# foe-scale.net
KiCad netlist of a schematic drawn in EAGLE
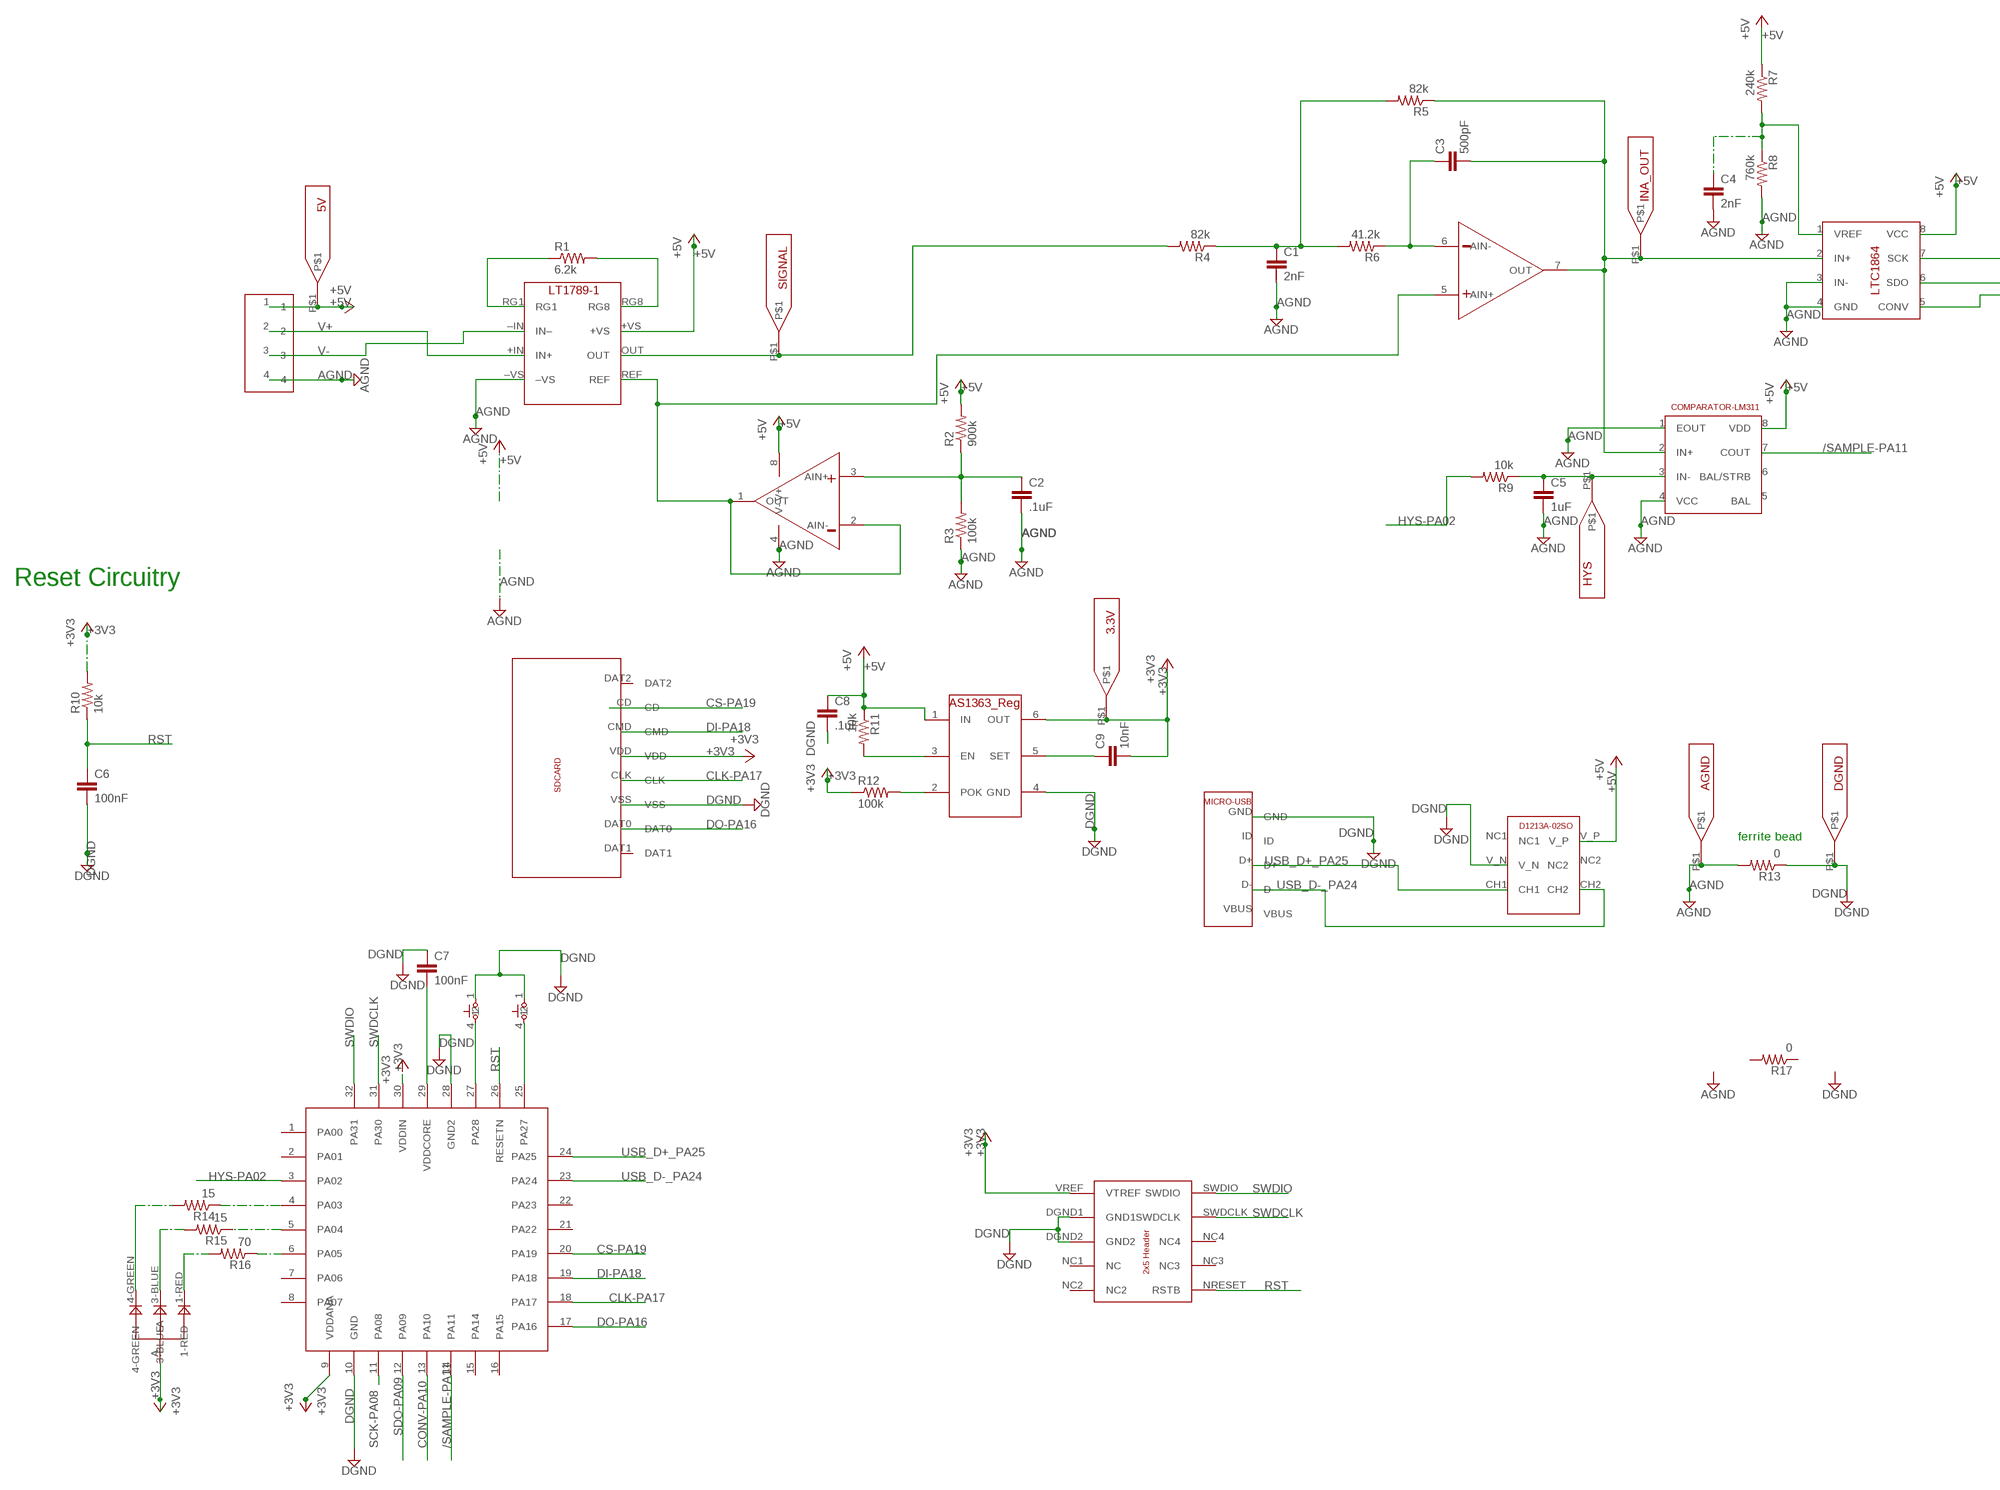
[diagram p0: schematic, sheet 1, part 1 of 2]
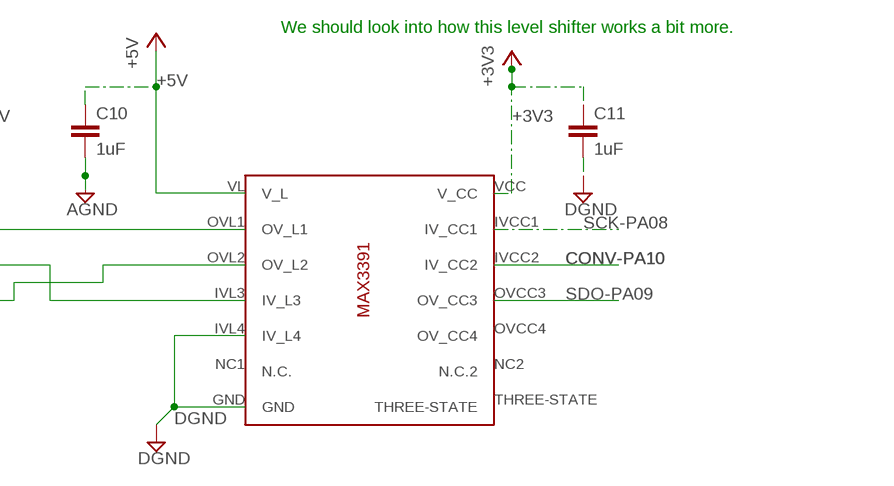
[diagram p1: schematic, sheet 1, part 2 of 2]

(export (version "E")
  (design (tool "Eeschema 10.0.6"))
  (components
    (comp (ref "3.3V")
      (value "TEST_POINT")
      (footprint "eagle-import:TEST_POINT")
      (libsource (lib "eagle-import") (part "TEST_POINT"))
    )
    (comp (ref "5V")
      (value "TEST_POINT")
      (footprint "eagle-import:TEST_POINT")
      (libsource (lib "eagle-import") (part "TEST_POINT"))
    )
    (comp (ref "AGND")
      (value "TEST_POINT")
      (footprint "eagle-import:TEST_POINT")
      (libsource (lib "eagle-import") (part "TEST_POINT"))
    )
    (comp (ref "AS1363")
      (value "3.3V_AS1363")
      (footprint "eagle-import:SOT23-6")
      (libsource (lib "eagle-import") (part "3.3V_AS1363"))
    )
    (comp (ref "C1")
      (value "2nF")
      (footprint "eagle-import:C0805K")
      (libsource (lib "eagle-import") (part "C-EUC0805K"))
    )
    (comp (ref "C2")
      (value ".1uF")
      (footprint "eagle-import:C0805K")
      (libsource (lib "eagle-import") (part "C-EUC0805K"))
    )
    (comp (ref "C3")
      (value "500pF")
      (footprint "eagle-import:C0805K")
      (libsource (lib "eagle-import") (part "C-EUC0805K"))
    )
    (comp (ref "C4")
      (value "2nF")
      (footprint "eagle-import:C0805K")
      (libsource (lib "eagle-import") (part "C-EUC0805K"))
    )
    (comp (ref "C5")
      (value "1uF")
      (footprint "eagle-import:C0805K")
      (libsource (lib "eagle-import") (part "C-EUC0805K"))
    )
    (comp (ref "C6")
      (value "100nF")
      (footprint "eagle-import:C0805K")
      (libsource (lib "eagle-import") (part "C-EUC0805K"))
    )
    (comp (ref "C7")
      (value "100nF")
      (footprint "eagle-import:C0805K")
      (libsource (lib "eagle-import") (part "C-EUC0805K"))
    )
    (comp (ref "C8")
      (value ".1uF")
      (footprint "eagle-import:C0805K")
      (libsource (lib "eagle-import") (part "C-EUC0805K"))
    )
    (comp (ref "C9")
      (value "10nF")
      (footprint "eagle-import:C0805K")
      (libsource (lib "eagle-import") (part "C-EUC0805K"))
    )
    (comp (ref "C10")
      (value "1uF")
      (footprint "eagle-import:C0805K")
      (libsource (lib "eagle-import") (part "C-EUC0805K"))
    )
    (comp (ref "C11")
      (value "1uF")
      (footprint "eagle-import:C0805K")
      (libsource (lib "eagle-import") (part "C-EUC0805K"))
    )
    (comp (ref "D1")
      (value "D1213A-DIODE-ARRAY")
      (footprint "eagle-import:SOT26-DIODE-ARRAY")
      (libsource (lib "eagle-import") (part "D1213A-DIODE-ARRAY"))
    )
    (comp (ref "DBG1")
      (value "DEBUGHEAD")
      (footprint "eagle-import:DEBUGHEAD")
      (libsource (lib "eagle-import") (part "DEBUGHEAD"))
    )
    (comp (ref "DGND")
      (value "TEST_POINT")
      (footprint "eagle-import:TEST_POINT")
      (libsource (lib "eagle-import") (part "TEST_POINT"))
    )
    (comp (ref "HYS")
      (value "TEST_POINT")
      (footprint "eagle-import:TEST_POINT")
      (libsource (lib "eagle-import") (part "TEST_POINT"))
    )
    (comp (ref "INA_OUT")
      (value "TEST_POINT")
      (footprint "eagle-import:TEST_POINT")
      (libsource (lib "eagle-import") (part "TEST_POINT"))
    )
    (comp (ref "R1")
      (value "6.2k")
      (footprint "eagle-import:R0805")
      (libsource (lib "eagle-import") (part "R-US_R0805"))
    )
    (comp (ref "R2")
      (value "900k")
      (footprint "eagle-import:R0805")
      (libsource (lib "eagle-import") (part "R-US_R0805"))
    )
    (comp (ref "R3")
      (value "100k")
      (footprint "eagle-import:R0805")
      (libsource (lib "eagle-import") (part "R-US_R0805"))
    )
    (comp (ref "R4")
      (value "82k")
      (footprint "eagle-import:R0805")
      (libsource (lib "eagle-import") (part "R-US_R0805"))
    )
    (comp (ref "R5")
      (value "82k")
      (footprint "eagle-import:R0805")
      (libsource (lib "eagle-import") (part "R-US_R0805"))
    )
    (comp (ref "R6")
      (value "41.2k")
      (footprint "eagle-import:R0805")
      (libsource (lib "eagle-import") (part "R-US_R0805"))
    )
    (comp (ref "R7")
      (value "240k")
      (footprint "eagle-import:R0805")
      (libsource (lib "eagle-import") (part "R-US_R0805"))
    )
    (comp (ref "R8")
      (value "760k")
      (footprint "eagle-import:R0805")
      (libsource (lib "eagle-import") (part "R-US_R0805"))
    )
    (comp (ref "R9")
      (value "10k")
      (footprint "eagle-import:R0805")
      (libsource (lib "eagle-import") (part "R-US_R0805"))
    )
    (comp (ref "R10")
      (value "10k")
      (footprint "eagle-import:R0805")
      (libsource (lib "eagle-import") (part "R-US_R0805"))
    )
    (comp (ref "R11")
      (value "10k")
      (footprint "eagle-import:R0805")
      (libsource (lib "eagle-import") (part "R-US_R0805"))
    )
    (comp (ref "R12")
      (value "100k")
      (footprint "eagle-import:R0805")
      (libsource (lib "eagle-import") (part "R-US_R0805"))
    )
    (comp (ref "R13")
      (value "0")
      (footprint "eagle-import:R0805")
      (libsource (lib "eagle-import") (part "R-US_R0805"))
    )
    (comp (ref "R14")
      (value "15")
      (footprint "eagle-import:R0805")
      (libsource (lib "eagle-import") (part "R-US_R0805"))
    )
    (comp (ref "R15")
      (value "15")
      (footprint "eagle-import:R0805")
      (libsource (lib "eagle-import") (part "R-US_R0805"))
    )
    (comp (ref "R16")
      (value "70")
      (footprint "eagle-import:R0805")
      (libsource (lib "eagle-import") (part "R-US_R0805"))
    )
    (comp (ref "R17")
      (value "0")
      (footprint "eagle-import:R0805")
      (libsource (lib "eagle-import") (part "R-US_R0805"))
    )
    (comp (ref "SIGNAL")
      (value "TEST_POINT")
      (footprint "eagle-import:TEST_POINT")
      (libsource (lib "eagle-import") (part "TEST_POINT"))
    )
    (comp (ref "U$1")
      (value "1X04")
      (footprint "eagle-import:1X04")
      (libsource (lib "eagle-import") (part "1X04"))
    )
    (comp (ref "U$2")
      (value "LT1789-1-INSTR-AMP")
      (footprint "eagle-import:S8-LT1789-1")
      (libsource (lib "eagle-import") (part "LT1789-1-INSTR-AMP"))
    )
    (comp (ref "U$3")
      (value "LMC6482")
      (footprint "eagle-import:SOIC8")
      (libsource (lib "eagle-import") (part "LMC6482"))
    )
    (comp (ref "U$6")
      (value "ADC-LTC1864")
      (footprint "eagle-import:SOIC8")
      (libsource (lib "eagle-import") (part "ADC-LTC1864"))
    )
    (comp (ref "U$7")
      (value "LEVEL-SHIFTER")
      (footprint "eagle-import:TSSOP-14")
      (libsource (lib "eagle-import") (part "LEVEL-SHIFTER"))
    )
    (comp (ref "U$8")
      (value "SDCARD_JACK")
      (footprint "eagle-import:MICRO_SDCARD")
      (libsource (lib "eagle-import") (part "SDCARD_JACK"))
    )
    (comp (ref "U$10")
      (value "RGBLED")
      (footprint "eagle-import:RGBLED")
      (libsource (lib "eagle-import") (part "RGBLED"))
    )
    (comp (ref "U$11")
      (value "BUTTON_THRU")
      (footprint "eagle-import:PUSHBTN")
      (libsource (lib "eagle-import") (part "BUTTON_THRU"))
    )
    (comp (ref "U$12")
      (value "BUTTON_THRU")
      (footprint "eagle-import:PUSHBTN")
      (libsource (lib "eagle-import") (part "BUTTON_THRU"))
    )
    (comp (ref "U$13")
      (value "MICRO-USB-CONNECTOR")
      (footprint "eagle-import:MICRO-USB-CONNECTOR")
      (libsource (lib "eagle-import") (part "MICRO-USB-CONNECTOR"))
    )
    (comp (ref "U1")
      (value "LM311")
      (footprint "eagle-import:SOIC8")
      (libsource (lib "eagle-import") (part "LM311"))
    )
    (comp (ref "U2")
      (value "SAMD21E")
      (footprint "eagle-import:TQFP32-08")
      (libsource (lib "eagle-import") (part "SAMD21E"))
    )
  )
  (nets
    (net (code "1") (name "+3V3") (class "Default")
      (node (ref "3.3V") (pin "P$1") (pinfunction "P$1_P$1") (pintype "bidirectional"))
      (node (ref "AS1363") (pin "6") (pinfunction "OUT_6") (pintype "bidirectional"))
      (node (ref "C11") (pin "1") (pinfunction "1_1") (pintype "passive"))
      (node (ref "C9") (pin "2") (pinfunction "2_2") (pintype "passive"))
      (node (ref "DBG1") (pin "VREF") (pinfunction "VTREF_VREF") (pintype "bidirectional"))
      (node (ref "R10") (pin "2") (pinfunction "2_2") (pintype "passive"))
      (node (ref "R12") (pin "1") (pinfunction "1_1") (pintype "passive"))
      (node (ref "U$10") (pin "A") (pinfunction "A_A") (pintype "bidirectional"))
      (node (ref "U$7") (pin "VCC") (pinfunction "V_CC_VCC") (pintype "bidirectional"))
      (node (ref "U$8") (pin "VDD") (pinfunction "VDD_VDD") (pintype "bidirectional"))
      (node (ref "U2") (pin "30") (pinfunction "VDDIN_30") (pintype "bidirectional"))
      (node (ref "U2") (pin "9") (pinfunction "VDDANA_9") (pintype "bidirectional"))
    )
    (net (code "2") (name "+5V") (class "Default")
      (node (ref "5V") (pin "P$1") (pinfunction "P$1_P$1") (pintype "bidirectional"))
      (node (ref "AS1363") (pin "1") (pinfunction "IN_1") (pintype "bidirectional"))
      (node (ref "C10") (pin "1") (pinfunction "1_1") (pintype "passive"))
      (node (ref "C8") (pin "1") (pinfunction "1_1") (pintype "passive"))
      (node (ref "D1") (pin "V_P") (pinfunction "V_P_V_P") (pintype "bidirectional"))
      (node (ref "R11") (pin "1") (pinfunction "1_1") (pintype "passive"))
      (node (ref "R2") (pin "2") (pinfunction "2_2") (pintype "passive"))
      (node (ref "R7") (pin "1") (pinfunction "1_1") (pintype "passive"))
      (node (ref "U$1") (pin "1") (pinfunction "1_1") (pintype "bidirectional"))
      (node (ref "U$2") (pin "+VS") (pinfunction "+VS_+VS") (pintype "bidirectional"))
      (node (ref "U$3") (pin "8") (pinfunction "V+_8") (pintype "bidirectional"))
      (node (ref "U$6") (pin "8") (pinfunction "VCC_8") (pintype "bidirectional"))
      (node (ref "U$7") (pin "VL") (pinfunction "V_L_VL") (pintype "bidirectional"))
      (node (ref "U1") (pin "8") (pinfunction "VDD_8") (pintype "bidirectional"))
    )
    (net (code "3") (name "/CLK-PA17") (class "Default")
      (node (ref "U$8") (pin "CLK") (pinfunction "CLK_CLK") (pintype "bidirectional"))
      (node (ref "U2") (pin "18") (pinfunction "PA17_18") (pintype "bidirectional"))
    )
    (net (code "4") (name "/CONV-PA10") (class "Default")
      (node (ref "U$7") (pin "IVCC2") (pinfunction "IV_CC2_IVCC2") (pintype "bidirectional"))
      (node (ref "U2") (pin "13") (pinfunction "PA10_13") (pintype "bidirectional"))
    )
    (net (code "5") (name "/CS-PA19") (class "Default")
      (node (ref "U$8") (pin "CD") (pinfunction "CD_CD") (pintype "bidirectional"))
      (node (ref "U2") (pin "20") (pinfunction "PA19_20") (pintype "bidirectional"))
    )
    (net (code "6") (name "/DI-PA18") (class "Default")
      (node (ref "U$8") (pin "CMD") (pinfunction "CMD_CMD") (pintype "bidirectional"))
      (node (ref "U2") (pin "19") (pinfunction "PA18_19") (pintype "bidirectional"))
    )
    (net (code "7") (name "/DO-PA16") (class "Default")
      (node (ref "U$8") (pin "DAT0") (pinfunction "DAT0_DAT0") (pintype "bidirectional"))
      (node (ref "U2") (pin "17") (pinfunction "PA16_17") (pintype "bidirectional"))
    )
    (net (code "8") (name "/HYS-PA02") (class "Default")
      (node (ref "R9") (pin "2") (pinfunction "2_2") (pintype "passive"))
      (node (ref "U2") (pin "3") (pinfunction "PA02_3") (pintype "bidirectional"))
    )
    (net (code "9") (name "/RST") (class "Default")
      (node (ref "C6") (pin "1") (pinfunction "1_1") (pintype "passive"))
      (node (ref "DBG1") (pin "NRESET") (pinfunction "RSTB_NRESET") (pintype "bidirectional"))
      (node (ref "R10") (pin "1") (pinfunction "1_1") (pintype "passive"))
      (node (ref "U2") (pin "26") (pinfunction "RESETN_26") (pintype "bidirectional"))
    )
    (net (code "10") (name "/SCK-PA08") (class "Default")
      (node (ref "U$7") (pin "IVCC1") (pinfunction "IV_CC1_IVCC1") (pintype "bidirectional"))
      (node (ref "U2") (pin "11") (pinfunction "PA08_11") (pintype "bidirectional"))
    )
    (net (code "11") (name "/SDO-PA09") (class "Default")
      (node (ref "U$7") (pin "OVCC3") (pinfunction "OV_CC3_OVCC3") (pintype "bidirectional"))
      (node (ref "U2") (pin "12") (pinfunction "PA09_12") (pintype "bidirectional"))
    )
    (net (code "12") (name "/SWDCLK") (class "Default")
      (node (ref "DBG1") (pin "SWDCLK") (pinfunction "SWDCLK_SWDCLK") (pintype "bidirectional"))
      (node (ref "U2") (pin "31") (pinfunction "PA30_31") (pintype "bidirectional"))
    )
    (net (code "13") (name "/SWDIO") (class "Default")
      (node (ref "DBG1") (pin "SWDIO") (pinfunction "SWDIO_SWDIO") (pintype "bidirectional"))
      (node (ref "U2") (pin "32") (pinfunction "PA31_32") (pintype "bidirectional"))
    )
    (net (code "14") (name "/USB_D+_PA25") (class "Default")
      (node (ref "D1") (pin "CH1") (pinfunction "CH1_CH1") (pintype "bidirectional"))
      (node (ref "U$13") (pin "D+") (pinfunction "D+_D+") (pintype "bidirectional"))
      (node (ref "U2") (pin "24") (pinfunction "PA25_24") (pintype "bidirectional"))
    )
    (net (code "15") (name "/USB_D-_PA24") (class "Default")
      (node (ref "D1") (pin "CH2") (pinfunction "CH2_CH2") (pintype "bidirectional"))
      (node (ref "U$13") (pin "D-") (pinfunction "D-_D-") (pintype "bidirectional"))
      (node (ref "U2") (pin "23") (pinfunction "PA24_23") (pintype "bidirectional"))
    )
    (net (code "16") (name "/V+") (class "Default")
      (node (ref "U$1") (pin "2") (pinfunction "2_2") (pintype "bidirectional"))
      (node (ref "U$2") (pin "+IN") (pinfunction "IN+_+IN") (pintype "bidirectional"))
    )
    (net (code "17") (name "/V-") (class "Default")
      (node (ref "U$1") (pin "3") (pinfunction "3_3") (pintype "bidirectional"))
      (node (ref "U$2") (pin "–IN") (pinfunction "IN–_–IN") (pintype "bidirectional"))
    )
    (net (code "18") (name "/{slash}SAMPLE-PA11") (class "Default")
      (node (ref "U1") (pin "7") (pinfunction "COUT_7") (pintype "bidirectional"))
      (node (ref "U2") (pin "14") (pinfunction "PA11_14") (pintype "bidirectional"))
    )
    (net (code "19") (name "AGND") (class "Default")
      (node (ref "AGND") (pin "P$1") (pinfunction "P$1_P$1") (pintype "bidirectional"))
      (node (ref "C1") (pin "2") (pinfunction "2_2") (pintype "passive"))
      (node (ref "C10") (pin "2") (pinfunction "2_2") (pintype "passive"))
      (node (ref "C2") (pin "2") (pinfunction "2_2") (pintype "passive"))
      (node (ref "C4") (pin "2") (pinfunction "2_2") (pintype "passive"))
      (node (ref "C5") (pin "2") (pinfunction "2_2") (pintype "passive"))
      (node (ref "R13") (pin "2") (pinfunction "2_2") (pintype "passive"))
      (node (ref "R3") (pin "1") (pinfunction "1_1") (pintype "passive"))
      (node (ref "R8") (pin "2") (pinfunction "2_2") (pintype "passive"))
      (node (ref "U$1") (pin "4") (pinfunction "4_4") (pintype "bidirectional"))
      (node (ref "U$2") (pin "–VS") (pinfunction "–VS_–VS") (pintype "bidirectional"))
      (node (ref "U$3") (pin "4") (pinfunction "V-_4") (pintype "bidirectional"))
      (node (ref "U$6") (pin "3") (pinfunction "IN-_3") (pintype "bidirectional"))
      (node (ref "U$6") (pin "4") (pinfunction "GND_4") (pintype "bidirectional"))
      (node (ref "U1") (pin "1") (pinfunction "EOUT_1") (pintype "bidirectional"))
      (node (ref "U1") (pin "4") (pinfunction "VCC_4") (pintype "bidirectional"))
    )
    (net (code "20") (name "DGND") (class "Default")
      (node (ref "AS1363") (pin "4") (pinfunction "GND_4") (pintype "bidirectional"))
      (node (ref "C11") (pin "2") (pinfunction "2_2") (pintype "passive"))
      (node (ref "C6") (pin "2") (pinfunction "2_2") (pintype "passive"))
      (node (ref "C7") (pin "1") (pinfunction "1_1") (pintype "passive"))
      (node (ref "C8") (pin "2") (pinfunction "2_2") (pintype "passive"))
      (node (ref "D1") (pin "V_N") (pinfunction "V_N_V_N") (pintype "bidirectional"))
      (node (ref "DBG1") (pin "DGND1") (pinfunction "GND1_DGND1") (pintype "bidirectional"))
      (node (ref "DBG1") (pin "DGND2") (pinfunction "GND2_DGND2") (pintype "bidirectional"))
      (node (ref "DGND") (pin "P$1") (pinfunction "P$1_P$1") (pintype "bidirectional"))
      (node (ref "R13") (pin "1") (pinfunction "1_1") (pintype "passive"))
      (node (ref "U$11") (pin "1") (pinfunction "1_1") (pintype "bidirectional"))
      (node (ref "U$12") (pin "1") (pinfunction "1_1") (pintype "bidirectional"))
      (node (ref "U$13") (pin "GND") (pinfunction "GND_GND") (pintype "bidirectional"))
      (node (ref "U$7") (pin "GND") (pinfunction "GND_GND") (pintype "bidirectional"))
      (node (ref "U$7") (pin "IVL4") (pinfunction "IV_L4_IVL4") (pintype "bidirectional"))
      (node (ref "U$8") (pin "VSS") (pinfunction "VSS_VSS") (pintype "bidirectional"))
      (node (ref "U2") (pin "10") (pinfunction "GND_10") (pintype "bidirectional"))
      (node (ref "U2") (pin "28") (pinfunction "GND2_28") (pintype "bidirectional"))
    )
    (net (code "21") (name "Net-(AS1363-EN)") (class "Default")
      (node (ref "AS1363") (pin "3") (pinfunction "EN_3") (pintype "bidirectional"))
      (node (ref "R11") (pin "2") (pinfunction "2_2") (pintype "passive"))
    )
    (net (code "22") (name "Net-(AS1363-POK)") (class "Default")
      (node (ref "AS1363") (pin "2") (pinfunction "POK_2") (pintype "bidirectional"))
      (node (ref "R12") (pin "2") (pinfunction "2_2") (pintype "passive"))
    )
    (net (code "23") (name "Net-(AS1363-SET)") (class "Default")
      (node (ref "AS1363") (pin "5") (pinfunction "SET_5") (pintype "bidirectional"))
      (node (ref "C9") (pin "1") (pinfunction "1_1") (pintype "passive"))
    )
    (net (code "24") (name "Net-(C1-Pad1)") (class "Default")
      (node (ref "C1") (pin "1") (pinfunction "1_1") (pintype "passive"))
      (node (ref "R4") (pin "1") (pinfunction "1_1") (pintype "passive"))
      (node (ref "R5") (pin "2") (pinfunction "2_2") (pintype "passive"))
      (node (ref "R6") (pin "2") (pinfunction "2_2") (pintype "passive"))
    )
    (net (code "25") (name "Net-(R1-Pad1)") (class "Default")
      (node (ref "R1") (pin "1") (pinfunction "1_1") (pintype "passive"))
      (node (ref "U$2") (pin "RG1") (pinfunction "RG1_RG1") (pintype "bidirectional"))
    )
    (net (code "26") (name "Net-(R1-Pad2)") (class "Default")
      (node (ref "R1") (pin "2") (pinfunction "2_2") (pintype "passive"))
      (node (ref "U$2") (pin "RG8") (pinfunction "RG8_RG8") (pintype "bidirectional"))
    )
    (net (code "27") (name "Net-(R4-Pad2)") (class "Default")
      (node (ref "R4") (pin "2") (pinfunction "2_2") (pintype "passive"))
      (node (ref "SIGNAL") (pin "P$1") (pinfunction "P$1_P$1") (pintype "bidirectional"))
      (node (ref "U$2") (pin "OUT") (pinfunction "OUT_OUT") (pintype "bidirectional"))
    )
    (net (code "28") (name "Net-(R14-Pad2)") (class "Default")
      (node (ref "R14") (pin "2") (pinfunction "2_2") (pintype "passive"))
      (node (ref "U$10") (pin "4-GREEN") (pinfunction "4-GREEN_4-GREEN") (pintype "bidirectional"))
    )
    (net (code "29") (name "Net-(R15-Pad2)") (class "Default")
      (node (ref "R15") (pin "2") (pinfunction "2_2") (pintype "passive"))
      (node (ref "U$10") (pin "3-BLUE") (pinfunction "3-BLUE_3-BLUE") (pintype "bidirectional"))
    )
    (net (code "30") (name "Net-(R16-Pad2)") (class "Default")
      (node (ref "R16") (pin "2") (pinfunction "2_2") (pintype "passive"))
      (node (ref "U$10") (pin "1-RED") (pinfunction "1-RED_1-RED") (pintype "bidirectional"))
    )
    (net (code "31") (name "Net-(U$3A-AIN+)") (class "Default")
      (node (ref "C2") (pin "1") (pinfunction "1_1") (pintype "passive"))
      (node (ref "R2") (pin "1") (pinfunction "1_1") (pintype "passive"))
      (node (ref "R3") (pin "2") (pinfunction "2_2") (pintype "passive"))
      (node (ref "U$3") (pin "3") (pinfunction "AIN+_3") (pintype "bidirectional"))
    )
    (net (code "32") (name "Net-(U$3A-AIN-)") (class "Default")
      (node (ref "U$2") (pin "REF") (pinfunction "REF_REF") (pintype "bidirectional"))
      (node (ref "U$3") (pin "1") (pinfunction "OUT_1") (pintype "bidirectional"))
      (node (ref "U$3") (pin "2") (pinfunction "AIN-_2") (pintype "bidirectional"))
      (node (ref "U$3") (pin "5") (pinfunction "AIN+_5") (pintype "bidirectional"))
    )
    (net (code "33") (name "Net-(U$3B-AIN-)") (class "Default")
      (node (ref "C3") (pin "1") (pinfunction "1_1") (pintype "passive"))
      (node (ref "R6") (pin "1") (pinfunction "1_1") (pintype "passive"))
      (node (ref "U$3") (pin "6") (pinfunction "AIN-_6") (pintype "bidirectional"))
    )
    (net (code "34") (name "Net-(U$3B-OUT)") (class "Default")
      (node (ref "C3") (pin "2") (pinfunction "2_2") (pintype "passive"))
      (node (ref "INA_OUT") (pin "P$1") (pinfunction "P$1_P$1") (pintype "bidirectional"))
      (node (ref "R5") (pin "1") (pinfunction "1_1") (pintype "passive"))
      (node (ref "U$3") (pin "7") (pinfunction "OUT_7") (pintype "bidirectional"))
      (node (ref "U$6") (pin "2") (pinfunction "IN+_2") (pintype "bidirectional"))
      (node (ref "U1") (pin "2") (pinfunction "IN+_2") (pintype "bidirectional"))
    )
    (net (code "35") (name "Net-(U$6-CONV)") (class "Default")
      (node (ref "U$6") (pin "5") (pinfunction "CONV_5") (pintype "bidirectional"))
      (node (ref "U$7") (pin "OVL2") (pinfunction "OV_L2_OVL2") (pintype "bidirectional"))
    )
    (net (code "36") (name "Net-(U$6-SCK)") (class "Default")
      (node (ref "U$6") (pin "7") (pinfunction "SCK_7") (pintype "bidirectional"))
      (node (ref "U$7") (pin "OVL1") (pinfunction "OV_L1_OVL1") (pintype "bidirectional"))
    )
    (net (code "37") (name "Net-(U$6-SDO)") (class "Default")
      (node (ref "U$6") (pin "6") (pinfunction "SDO_6") (pintype "bidirectional"))
      (node (ref "U$7") (pin "IVL3") (pinfunction "IV_L3_IVL3") (pintype "bidirectional"))
    )
    (net (code "38") (name "Net-(U$6-VREF)") (class "Default")
      (node (ref "C4") (pin "1") (pinfunction "1_1") (pintype "passive"))
      (node (ref "R7") (pin "2") (pinfunction "2_2") (pintype "passive"))
      (node (ref "R8") (pin "1") (pinfunction "1_1") (pintype "passive"))
      (node (ref "U$6") (pin "1") (pinfunction "VREF_1") (pintype "bidirectional"))
    )
    (net (code "39") (name "Net-(U$11-2)") (class "Default")
      (node (ref "U$11") (pin "4") (pinfunction "2_4") (pintype "bidirectional"))
      (node (ref "U2") (pin "25") (pinfunction "PA27_25") (pintype "bidirectional"))
    )
    (net (code "40") (name "Net-(U$12-2)") (class "Default")
      (node (ref "U$12") (pin "4") (pinfunction "2_4") (pintype "bidirectional"))
      (node (ref "U2") (pin "27") (pinfunction "PA28_27") (pintype "bidirectional"))
    )
    (net (code "41") (name "Net-(U1-IN-)") (class "Default")
      (node (ref "C5") (pin "1") (pinfunction "1_1") (pintype "passive"))
      (node (ref "HYS") (pin "P$1") (pinfunction "P$1_P$1") (pintype "bidirectional"))
      (node (ref "R9") (pin "1") (pinfunction "1_1") (pintype "passive"))
      (node (ref "U1") (pin "3") (pinfunction "IN-_3") (pintype "bidirectional"))
    )
    (net (code "42") (name "Net-(U2-PA03)") (class "Default")
      (node (ref "R14") (pin "1") (pinfunction "1_1") (pintype "passive"))
      (node (ref "U2") (pin "4") (pinfunction "PA03_4") (pintype "bidirectional"))
    )
    (net (code "43") (name "Net-(U2-PA04)") (class "Default")
      (node (ref "R15") (pin "1") (pinfunction "1_1") (pintype "passive"))
      (node (ref "U2") (pin "5") (pinfunction "PA04_5") (pintype "bidirectional"))
    )
    (net (code "44") (name "Net-(U2-PA05)") (class "Default")
      (node (ref "R16") (pin "1") (pinfunction "1_1") (pintype "passive"))
      (node (ref "U2") (pin "6") (pinfunction "PA05_6") (pintype "bidirectional"))
    )
    (net (code "45") (name "Net-(U2-VDDCORE)") (class "Default")
      (node (ref "C7") (pin "2") (pinfunction "2_2") (pintype "passive"))
      (node (ref "U2") (pin "29") (pinfunction "VDDCORE_29") (pintype "bidirectional"))
    )
    (net (code "46") (name "unconnected-(D1-PadNC1)") (class "Default")
      (node (ref "D1") (pin "NC1") (pinfunction "NC1_NC1") (pintype "bidirectional"))
    )
    (net (code "47") (name "unconnected-(D1-PadNC2)") (class "Default")
      (node (ref "D1") (pin "NC2") (pinfunction "NC2_NC2") (pintype "bidirectional"))
    )
    (net (code "48") (name "unconnected-(DBG1-NC-PadNC1)") (class "Default")
      (node (ref "DBG1") (pin "NC1") (pinfunction "NC_NC1") (pintype "bidirectional"))
    )
    (net (code "49") (name "unconnected-(DBG1-PadNC2)") (class "Default")
      (node (ref "DBG1") (pin "NC2") (pinfunction "NC2_NC2") (pintype "bidirectional"))
    )
    (net (code "50") (name "unconnected-(DBG1-PadNC3)") (class "Default")
      (node (ref "DBG1") (pin "NC3") (pinfunction "NC3_NC3") (pintype "bidirectional"))
    )
    (net (code "51") (name "unconnected-(DBG1-PadNC4)") (class "Default")
      (node (ref "DBG1") (pin "NC4") (pinfunction "NC4_NC4") (pintype "bidirectional"))
    )
    (net (code "52") (name "unconnected-(R17-Pad1)") (class "Default")
      (node (ref "R17") (pin "1") (pinfunction "1_1") (pintype "passive"))
    )
    (net (code "53") (name "unconnected-(R17-Pad2)") (class "Default")
      (node (ref "R17") (pin "2") (pinfunction "2_2") (pintype "passive"))
    )
    (net (code "54") (name "unconnected-(U$7-N.C.-PadNC1)") (class "Default")
      (node (ref "U$7") (pin "NC1") (pinfunction "N.C._NC1") (pintype "bidirectional"))
    )
    (net (code "55") (name "unconnected-(U$7-N.C.2-PadNC2)") (class "Default")
      (node (ref "U$7") (pin "NC2") (pinfunction "N.C.2_NC2") (pintype "bidirectional"))
    )
    (net (code "56") (name "unconnected-(U$7-OV_CC4-PadOVCC4)") (class "Default")
      (node (ref "U$7") (pin "OVCC4") (pinfunction "OV_CC4_OVCC4") (pintype "bidirectional"))
    )
    (net (code "57") (name "unconnected-(U$7-PadTHREE-STATE)") (class "Default")
      (node (ref "U$7") (pin "THREE-STATE") (pinfunction "THREE-STATE_THREE-STATE") (pintype "bidirectional"))
    )
    (net (code "58") (name "unconnected-(U$8-PadDAT1)") (class "Default")
      (node (ref "U$8") (pin "DAT1") (pinfunction "DAT1_DAT1") (pintype "bidirectional"))
    )
    (net (code "59") (name "unconnected-(U$8-PadDAT2)") (class "Default")
      (node (ref "U$8") (pin "DAT2") (pinfunction "DAT2_DAT2") (pintype "bidirectional"))
    )
    (net (code "60") (name "unconnected-(U$13-PadID)") (class "Default")
      (node (ref "U$13") (pin "ID") (pinfunction "ID_ID") (pintype "bidirectional"))
    )
    (net (code "61") (name "unconnected-(U$13-PadVBUS)") (class "Default")
      (node (ref "U$13") (pin "VBUS") (pinfunction "VBUS_VBUS") (pintype "bidirectional"))
    )
    (net (code "62") (name "unconnected-(U1-BAL-Pad5)") (class "Default")
      (node (ref "U1") (pin "5") (pinfunction "BAL_5") (pintype "bidirectional"))
    )
    (net (code "63") (name "unconnected-(U1-BAL{slash}STRB-Pad6)") (class "Default")
      (node (ref "U1") (pin "6") (pinfunction "BAL/STRB_6") (pintype "bidirectional"))
    )
    (net (code "64") (name "unconnected-(U2-PA00-Pad1)") (class "Default")
      (node (ref "U2") (pin "1") (pinfunction "PA00_1") (pintype "bidirectional"))
    )
    (net (code "65") (name "unconnected-(U2-PA01-Pad2)") (class "Default")
      (node (ref "U2") (pin "2") (pinfunction "PA01_2") (pintype "bidirectional"))
    )
    (net (code "66") (name "unconnected-(U2-PA06-Pad7)") (class "Default")
      (node (ref "U2") (pin "7") (pinfunction "PA06_7") (pintype "bidirectional"))
    )
    (net (code "67") (name "unconnected-(U2-PA07-Pad8)") (class "Default")
      (node (ref "U2") (pin "8") (pinfunction "PA07_8") (pintype "bidirectional"))
    )
    (net (code "68") (name "unconnected-(U2-PA14-Pad15)") (class "Default")
      (node (ref "U2") (pin "15") (pinfunction "PA14_15") (pintype "bidirectional"))
    )
    (net (code "69") (name "unconnected-(U2-PA15-Pad16)") (class "Default")
      (node (ref "U2") (pin "16") (pinfunction "PA15_16") (pintype "bidirectional"))
    )
    (net (code "70") (name "unconnected-(U2-PA22-Pad21)") (class "Default")
      (node (ref "U2") (pin "21") (pinfunction "PA22_21") (pintype "bidirectional"))
    )
    (net (code "71") (name "unconnected-(U2-PA23-Pad22)") (class "Default")
      (node (ref "U2") (pin "22") (pinfunction "PA23_22") (pintype "bidirectional"))
    )
  )
)
